# 830-00011_Microhard_Module_Breakout_Boar.net
KiCad netlist of a schematic drawn in Altium Designer
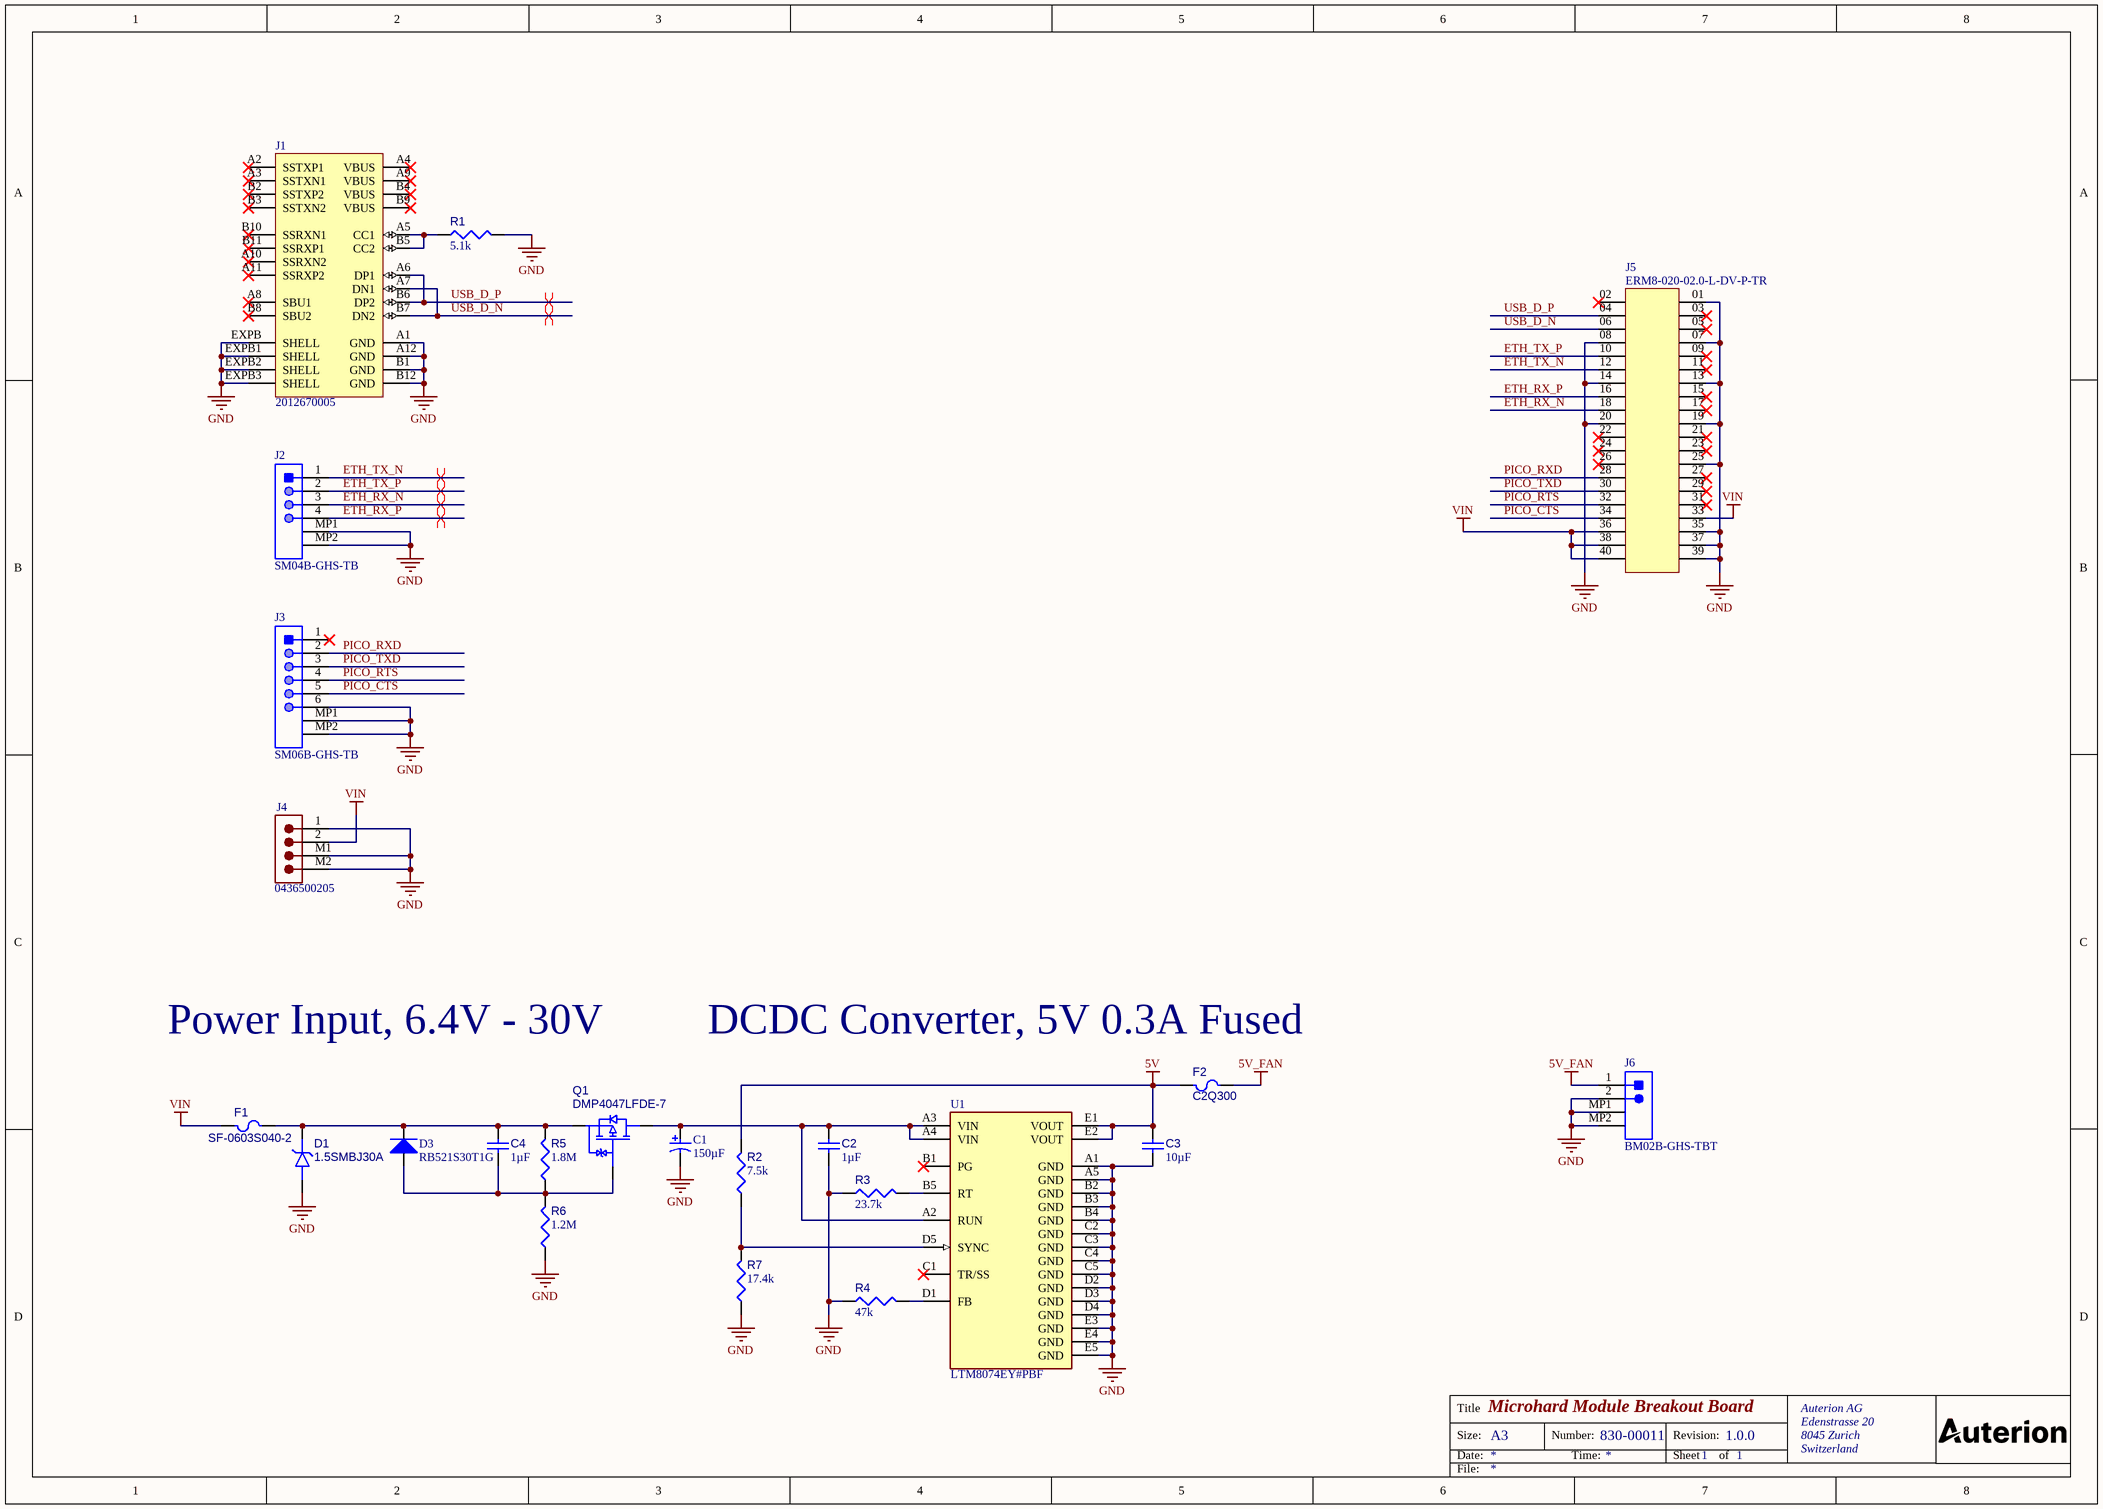
[diagram p0: 830-00011 Microhard Module Breakout Board.SchDoc]

(export (version "E")
  (design (tool "Eeschema 10.0.6"))
  (components
    (comp (ref "C1")
      (value "150µF")
      (footprint "CAPAE6866X82L")
      (description "CAP ALUM 150UF 20% 35V SMD")
      (fields
        (field (name "MANUFACTURER") "Nichicon")
        (field (name "MANUFACTURER PART NUMBER") "UCM1V151MCL1GS")
      )
      (libsource (lib "Auterion AG") (part "CAP-P-2"))
    )
    (comp (ref "C2")
      (value "1µF")
      (footprint "CAPC0603(1608)100_L")
      (description "CAP CER 1UF 50V X5R 0603")
      (fields
        (field (name "TOLERANCE") "10%")
        (field (name "MANUFACTURER PART NUMBER") "C1608X5R1H105K080AB")
      )
      (libsource (lib "Auterion AG") (part "CAP-NP-2"))
    )
    (comp (ref "C3")
      (value "10µF")
      (footprint "CAPC0805(2012)145_L")
      (description "CAP CER 10UF 16V X7R 0805")
      (fields (field (name "TOLERANCE") "20%") (field (name "MANUFACTURER") "Taiyo Yuden"))
      (libsource (lib "Auterion AG") (part "CAP-NP-2"))
    )
    (comp (ref "C4")
      (value "1µF")
      (footprint "CAPC0402(1005)60_L")
      (description "CAP CER 1UF 35V X5R 0402")
      (fields (field (name "TOLERANCE") "10%") (field (name "MANUFACTURER") "TDK Corporation"))
      (libsource (lib "Auterion AG") (part "CAP-NP-2"))
    )
    (comp (ref "D1")
      (value "1.5SMBJ30A")
      (footprint "JCET-SMB-2_N")
      (description "TVS Diode Single Uni-Dir 30V 1.5KW 2-Pin SMB T/R")
      (fields (field (name "MANUFACTURER") "Bourns"))
      (libsource (lib "Auterion AG") (part "D-TVS-AK-2"))
    )
    (comp (ref "D3")
      (value "RB521S30T1G")
      (footprint "ONSC-SOD-523-2-502-01_V")
      (description "Rectifier Diode, Schottky, 1 Phase, 1 Element, 0.2A, 30V V(RRM), Silicon")
      (fields (field (name "MANUFACTURER") "onsemi"))
      (libsource (lib "Auterion AG") (part "ONSC-D-K1A2-2"))
    )
    (comp (ref "F1")
      (value "SF-0603S040-2")
      (footprint "RESC0603(1608)_L")
      (description "Electric Fuse, Slow Blow, 0.4A, 35VAC, 50VDC, 50A (IR), Surface Mount, 0603")
      (fields (field (name "MANUFACTURER") "Bourns Inc."))
      (libsource (lib "Auterion AG") (part "FUSE-2"))
    )
    (comp (ref "F2")
      (value "C2Q300")
      (footprint "RESC0603(1608)_L")
      (description "Electric Fuse, Very Fast Blow, 0.3A, 32VAC, 63VDC, 35A (IR), Surface Mount, 0603")
      (fields
        (field (name "MANUFACTURER PART NUMBER") "C2Q 300")
        (field (name "MANUFACTURER") "Bel Fuse Inc.")
      )
      (libsource (lib "Auterion AG") (part "FUSE-2"))
    )
    (comp (ref "J1")
      (value "2012670005")
      (footprint "2012670005")
      (description "USB Connector, 24 Contact(s), Female, Right Angle, Surface Mount Terminal, Locking, Receptacle")
      (fields
        (field (name "MANUFACTURER") "Molex")
        (field (name "UPDATED BY") "aklimaj")
        (field (name "SOURCE") "skynode_v2_base.SCHLIB")
        (field (name "CREATED BY") "aklimaj")
      )
      (libsource (lib "Auterion AG") (part "30530"))
    )
    (comp (ref "J2")
      (value "SM04B-GHS-TB")
      (footprint "JST-SM04B-GHS-TB")
      (description "4 Positions Header Connector 1.25mm SMD Right Angle")
      (fields (field (name "SFL PART NUMBER") "10751") (field (name "MANUFACTURER") "JST"))
      (libsource (lib "Auterion AG") (part "SM04B-GHS-TB"))
    )
    (comp (ref "J3")
      (value "SM06B-GHS-TB")
      (footprint "JST-SM06B-GHS-TB_V")
      (fields
        (field (name "SFL PART NUMBER") "10703")
        (field (name "MANUFACTURER PART NUMBER") "SM06B-GHS-TB(LF)(SN)")
        (field (name "MANUFACTURER") "JST")
      )
      (libsource (lib "Auterion AG") (part "SM06B-GHS-TB"))
    )
    (comp (ref "J4")
      (value "0436500205")
      (footprint "SHDRRA2W64P300_2X1_965X990H437")
      (description "CONN MALE HEADER R/A 2POS 3MM")
      (fields (field (name "MANUFACTURER") "Molex"))
      (libsource (lib "Auterion AG") (part "CONN_HDR_1x2_MALE_3.00MM_RA_TH"))
    )
    (comp (ref "J5")
      (value "ERM8-020-02.0-L-DV-P-TR")
      (footprint "FP-ERM8-020-02_0-L-DV-TR-MFG")
      (fields (field (name "MANUFACTURER") "Samtec"))
      (libsource (lib "Auterion AG") (part "ERF8-020-XX.X-X-DV-K-XX"))
    )
    (comp (ref "J6")
      (value "BM02B-GHS-TBT")
      (footprint "JST-BM02B-GHS-TBT_V")
      (fields (field (name "MANUFACTURER") "JST Sales America Inc."))
      (libsource (lib "Auterion AG") (part "B2W - BM02B-GHS-TBT"))
    )
    (comp (ref "Q1")
      (value "DMP4047LFDE-7")
      (footprint "DMP2066UFDE7")
      (description "MOSFET P-CH 40V 3.3A 6UDFN")
      (fields (field (name "POWER") "700mW") (field (name "MANUFACTURER") "Diodes Incorporated"))
      (libsource (lib "Auterion AG") (part "CMP-00006-6"))
    )
    (comp (ref "R1")
      (value "5.1k")
      (footprint "RESC0402(1005)_L")
      (fields
        (field (name "MANUFACTURER PART NUMBER") "RC0402JR-075K1L")
        (field (name "TOLERANCE") "5%")
        (field (name "POWER") "63mW")
      )
      (libsource (lib "Auterion AG") (part "RES-2"))
    )
    (comp (ref "R2")
      (value "7.5k")
      (footprint "RESC0402(1005)_L")
      (description "RES 7.5K OHM 1% 1/16W 0402")
      (fields (field (name "POWER") "63mW") (field (name "TOLERANCE") "1%"))
      (libsource (lib "Auterion AG") (part "RES-2"))
    )
    (comp (ref "R3")
      (value "23.7k")
      (footprint "RESC0402(1005)_L")
      (description "RES 23.7K OHM 1% 1/16W 0402")
      (fields (field (name "POWER") "63mW") (field (name "TOLERANCE") "1%"))
      (libsource (lib "Auterion AG") (part "RES-2"))
    )
    (comp (ref "R4")
      (value "47k")
      (footprint "RESC0402(1005)_L")
      (fields
        (field (name "MANUFACTURER") "Yageo")
        (field (name "TOLERANCE") "1%")
        (field (name "MANUFACTURER PART NUMBER") "RC0402FR-0747KL")
      )
      (libsource (lib "Auterion AG") (part "RES-2"))
    )
    (comp (ref "R5")
      (value "1.8M")
      (footprint "RESC0402(1005)_L")
      (description "RES SMD 1.8M OHM 1% 1/16W 0402")
      (fields (field (name "MANUFACTURER") "Samsung Electro-Mechanics") (field (name "POWER") "63mW"))
      (libsource (lib "Auterion AG") (part "RES-2"))
    )
    (comp (ref "R6")
      (value "1.2M")
      (footprint "RESC0402(1005)_L")
      (fields
        (field (name "MANUFACTURER") "Yageo")
        (field (name "MANUFACTURER PART NUMBER") "RC0402FR-071M2L")
        (field (name "TOLERANCE") "1%")
      )
      (libsource (lib "Auterion AG") (part "RES-2"))
    )
    (comp (ref "R7")
      (value "17.4k")
      (footprint "RESC0402(1005)_L")
      (description "RES SMD 17.4K OHM 1% 1/16W 0402")
      (fields (field (name "MANUFACTURER") "Vishay Dale") (field (name "TOLERANCE") "1%"))
      (libsource (lib "Auterion AG") (part "RES-2"))
    )
    (comp (ref "U1")
      (value "LTM8074EY#PBF")
      (footprint "FP-BGA-25-05-08-1566-MFG")
      (description "Switching Regulator, Current-mode, 2200kHz Switching Freq-Max, PBGA25")
      (fields (field (name "MANUFACTURER") "Analog Devices"))
      (libsource (lib "Auterion AG") (part "9e9da4b837be4f4c72679088a9770a1"))
    )
  )
  (nets
    (net (code "1") (name "/ETH_RX_N") (class "Default")
      (node (ref "J2") (pin "3") (pinfunction "3_3") (pintype "passive"))
      (node (ref "J5") (pin "18") (pinfunction "18_18") (pintype "passive"))
    )
    (net (code "2") (name "/ETH_RX_P") (class "Default")
      (node (ref "J2") (pin "4") (pinfunction "4_4") (pintype "passive"))
      (node (ref "J5") (pin "16") (pinfunction "16_16") (pintype "passive"))
    )
    (net (code "3") (name "/ETH_TX_N") (class "Default")
      (node (ref "J2") (pin "1") (pinfunction "1_1") (pintype "passive"))
      (node (ref "J5") (pin "12") (pinfunction "12_12") (pintype "passive"))
    )
    (net (code "4") (name "/ETH_TX_P") (class "Default")
      (node (ref "J2") (pin "2") (pinfunction "2_2") (pintype "passive"))
      (node (ref "J5") (pin "10") (pinfunction "10_10") (pintype "passive"))
    )
    (net (code "5") (name "/PICO_CTS") (class "Default")
      (node (ref "J3") (pin "5") (pinfunction "5_5") (pintype "passive"))
      (node (ref "J5") (pin "34") (pinfunction "34_34") (pintype "passive"))
    )
    (net (code "6") (name "/PICO_RTS") (class "Default")
      (node (ref "J3") (pin "4") (pinfunction "4_4") (pintype "passive"))
      (node (ref "J5") (pin "32") (pinfunction "32_32") (pintype "passive"))
    )
    (net (code "7") (name "/PICO_RXD") (class "Default")
      (node (ref "J3") (pin "2") (pinfunction "2_2") (pintype "passive"))
      (node (ref "J5") (pin "28") (pinfunction "28_28") (pintype "passive"))
    )
    (net (code "8") (name "/PICO_TXD") (class "Default")
      (node (ref "J3") (pin "3") (pinfunction "3_3") (pintype "passive"))
      (node (ref "J5") (pin "30") (pinfunction "30_30") (pintype "passive"))
    )
    (net (code "9") (name "/USB_D_N") (class "Default")
      (node (ref "J1") (pin "A7") (pinfunction "DN1_A7") (pintype "bidirectional"))
      (node (ref "J1") (pin "B7") (pinfunction "DN2_B7") (pintype "bidirectional"))
      (node (ref "J5") (pin "06") (pinfunction "06_06") (pintype "passive"))
    )
    (net (code "10") (name "/USB_D_P") (class "Default")
      (node (ref "J1") (pin "A6") (pinfunction "DP1_A6") (pintype "bidirectional"))
      (node (ref "J1") (pin "B6") (pinfunction "DP2_B6") (pintype "bidirectional"))
      (node (ref "J5") (pin "04") (pinfunction "04_04") (pintype "passive"))
    )
    (net (code "11") (name "5V") (class "Default")
      (node (ref "C3") (pin "2") (pinfunction "2_2") (pintype "passive"))
      (node (ref "F2") (pin "1") (pinfunction "1_1") (pintype "passive"))
      (node (ref "R2") (pin "2") (pinfunction "2_2") (pintype "passive"))
      (node (ref "U1") (pin "E1") (pinfunction "VOUT_E1") (pintype "power_in"))
      (node (ref "U1") (pin "E2") (pinfunction "VOUT_E2") (pintype "power_in"))
    )
    (net (code "12") (name "5V_FAN") (class "Default")
      (node (ref "F2") (pin "2") (pinfunction "2_2") (pintype "passive"))
      (node (ref "J6") (pin "1") (pinfunction "1_1") (pintype "passive"))
    )
    (net (code "13") (name "GND") (class "Default")
      (node (ref "C1") (pin "2") (pinfunction "2_2") (pintype "passive"))
      (node (ref "C2") (pin "1") (pinfunction "1_1") (pintype "passive"))
      (node (ref "C3") (pin "1") (pinfunction "1_1") (pintype "passive"))
      (node (ref "D1") (pin "A") (pinfunction "A_A") (pintype "passive"))
      (node (ref "J1") (pin "A1") (pinfunction "GND_A1") (pintype "power_in"))
      (node (ref "J1") (pin "A12") (pinfunction "GND_A12") (pintype "power_in"))
      (node (ref "J1") (pin "B1") (pinfunction "GND_B1") (pintype "power_in"))
      (node (ref "J1") (pin "B12") (pinfunction "GND_B12") (pintype "power_in"))
      (node (ref "J1") (pin "EXPB") (pinfunction "SHELL_EXPB") (pintype "power_in"))
      (node (ref "J1") (pin "EXPB1") (pinfunction "SHELL_EXPB1") (pintype "power_in"))
      (node (ref "J1") (pin "EXPB2") (pinfunction "SHELL_EXPB2") (pintype "power_in"))
      (node (ref "J1") (pin "EXPB3") (pinfunction "SHELL_EXPB3") (pintype "power_in"))
      (node (ref "J2") (pin "MP1") (pinfunction "MP1_MP1") (pintype "passive"))
      (node (ref "J2") (pin "MP2") (pinfunction "MP2_MP2") (pintype "passive"))
      (node (ref "J3") (pin "6") (pinfunction "6_6") (pintype "passive"))
      (node (ref "J3") (pin "MP1") (pinfunction "MP1_MP1") (pintype "passive"))
      (node (ref "J3") (pin "MP2") (pinfunction "MP2_MP2") (pintype "passive"))
      (node (ref "J4") (pin "1") (pinfunction "1_1") (pintype "passive"))
      (node (ref "J4") (pin "M1") (pinfunction "M1_M1") (pintype "passive"))
      (node (ref "J4") (pin "M2") (pinfunction "M2_M2") (pintype "passive"))
      (node (ref "J5") (pin "01") (pinfunction "01_01") (pintype "passive"))
      (node (ref "J5") (pin "07") (pinfunction "07_07") (pintype "passive"))
      (node (ref "J5") (pin "08") (pinfunction "08_08") (pintype "passive"))
      (node (ref "J5") (pin "13") (pinfunction "13_13") (pintype "passive"))
      (node (ref "J5") (pin "14") (pinfunction "14_14") (pintype "passive"))
      (node (ref "J5") (pin "19") (pinfunction "19_19") (pintype "passive"))
      (node (ref "J5") (pin "20") (pinfunction "20_20") (pintype "passive"))
      (node (ref "J5") (pin "25") (pinfunction "25_25") (pintype "passive"))
      (node (ref "J5") (pin "35") (pinfunction "35_35") (pintype "passive"))
      (node (ref "J5") (pin "37") (pinfunction "37_37") (pintype "passive"))
      (node (ref "J5") (pin "39") (pinfunction "39_39") (pintype "passive"))
      (node (ref "J6") (pin "2") (pinfunction "2_2") (pintype "passive"))
      (node (ref "J6") (pin "MP1") (pinfunction "MP1_MP1") (pintype "passive"))
      (node (ref "J6") (pin "MP2") (pinfunction "MP2_MP2") (pintype "passive"))
      (node (ref "R1") (pin "2") (pinfunction "2_2") (pintype "passive"))
      (node (ref "R3") (pin "1") (pinfunction "1_1") (pintype "passive"))
      (node (ref "R4") (pin "1") (pinfunction "1_1") (pintype "passive"))
      (node (ref "R6") (pin "1") (pinfunction "1_1") (pintype "passive"))
      (node (ref "R7") (pin "1") (pinfunction "1_1") (pintype "passive"))
      (node (ref "U1") (pin "A1") (pinfunction "GND_A1") (pintype "power_in"))
      (node (ref "U1") (pin "A5") (pinfunction "GND_A5") (pintype "power_in"))
      (node (ref "U1") (pin "B2") (pinfunction "GND_B2") (pintype "power_in"))
      (node (ref "U1") (pin "B3") (pinfunction "GND_B3") (pintype "power_in"))
      (node (ref "U1") (pin "B4") (pinfunction "GND_B4") (pintype "power_in"))
      (node (ref "U1") (pin "C2") (pinfunction "GND_C2") (pintype "power_in"))
      (node (ref "U1") (pin "C3") (pinfunction "GND_C3") (pintype "power_in"))
      (node (ref "U1") (pin "C4") (pinfunction "GND_C4") (pintype "power_in"))
      (node (ref "U1") (pin "C5") (pinfunction "GND_C5") (pintype "power_in"))
      (node (ref "U1") (pin "D2") (pinfunction "GND_D2") (pintype "power_in"))
      (node (ref "U1") (pin "D3") (pinfunction "GND_D3") (pintype "power_in"))
      (node (ref "U1") (pin "D4") (pinfunction "GND_D4") (pintype "power_in"))
      (node (ref "U1") (pin "E3") (pinfunction "GND_E3") (pintype "power_in"))
      (node (ref "U1") (pin "E4") (pinfunction "GND_E4") (pintype "power_in"))
      (node (ref "U1") (pin "E5") (pinfunction "GND_E5") (pintype "power_in"))
    )
    (net (code "14") (name "Net-(D3-A)") (class "Default")
      (node (ref "C4") (pin "1") (pinfunction "1_1") (pintype "passive"))
      (node (ref "D3") (pin "2") (pinfunction "A_2") (pintype "passive"))
      (node (ref "Q1") (pin "G") (pinfunction "G_G") (pintype "passive"))
      (node (ref "R5") (pin "1") (pinfunction "1_1") (pintype "passive"))
      (node (ref "R6") (pin "2") (pinfunction "2_2") (pintype "passive"))
    )
    (net (code "15") (name "Net-(D3-K)") (class "Default")
      (node (ref "C4") (pin "2") (pinfunction "2_2") (pintype "passive"))
      (node (ref "D1") (pin "K") (pinfunction "K_K") (pintype "passive"))
      (node (ref "D3") (pin "1") (pinfunction "K_1") (pintype "passive"))
      (node (ref "F1") (pin "2") (pinfunction "2_2") (pintype "passive"))
      (node (ref "Q1") (pin "S") (pinfunction "S_S") (pintype "passive"))
      (node (ref "R5") (pin "2") (pinfunction "2_2") (pintype "passive"))
    )
    (net (code "16") (name "Net-(J1-CC1)") (class "Default")
      (node (ref "J1") (pin "A5") (pinfunction "CC1_A5") (pintype "bidirectional"))
      (node (ref "J1") (pin "B5") (pinfunction "CC2_B5") (pintype "bidirectional"))
      (node (ref "R1") (pin "1") (pinfunction "1_1") (pintype "passive"))
    )
    (net (code "17") (name "Net-(U1-FB)") (class "Default")
      (node (ref "R4") (pin "2") (pinfunction "2_2") (pintype "passive"))
      (node (ref "U1") (pin "D1") (pinfunction "FB_D1") (pintype "passive"))
    )
    (net (code "18") (name "Net-(U1-RT)") (class "Default")
      (node (ref "R3") (pin "2") (pinfunction "2_2") (pintype "passive"))
      (node (ref "U1") (pin "B5") (pinfunction "RT_B5") (pintype "passive"))
    )
    (net (code "19") (name "Net-(U1-RUN)") (class "Default")
      (node (ref "C1") (pin "1") (pinfunction "1_1") (pintype "passive"))
      (node (ref "C2") (pin "2") (pinfunction "2_2") (pintype "passive"))
      (node (ref "Q1") (pin "D") (pinfunction "D_D") (pintype "passive"))
      (node (ref "U1") (pin "A2") (pinfunction "RUN_A2") (pintype "passive"))
      (node (ref "U1") (pin "A3") (pinfunction "VIN_A3") (pintype "power_in"))
      (node (ref "U1") (pin "A4") (pinfunction "VIN_A4") (pintype "power_in"))
    )
    (net (code "20") (name "Net-(U1-SYNC)") (class "Default")
      (node (ref "R2") (pin "1") (pinfunction "1_1") (pintype "passive"))
      (node (ref "R7") (pin "2") (pinfunction "2_2") (pintype "passive"))
      (node (ref "U1") (pin "D5") (pinfunction "SYNC_D5") (pintype "input"))
    )
    (net (code "21") (name "VIN") (class "Default")
      (node (ref "F1") (pin "1") (pinfunction "1_1") (pintype "passive"))
      (node (ref "J4") (pin "2") (pinfunction "2_2") (pintype "passive"))
      (node (ref "J5") (pin "33") (pinfunction "33_33") (pintype "passive"))
      (node (ref "J5") (pin "36") (pinfunction "36_36") (pintype "passive"))
      (node (ref "J5") (pin "38") (pinfunction "38_38") (pintype "passive"))
      (node (ref "J5") (pin "40") (pinfunction "40_40") (pintype "passive"))
    )
    (net (code "22") (name "unconnected-(J1-SBU1-PadA8)") (class "Default")
      (node (ref "J1") (pin "A8") (pinfunction "SBU1_A8") (pintype "passive+no_connect"))
    )
    (net (code "23") (name "unconnected-(J1-SBU2-PadB8)") (class "Default")
      (node (ref "J1") (pin "B8") (pinfunction "SBU2_B8") (pintype "passive+no_connect"))
    )
    (net (code "24") (name "unconnected-(J1-SSRXN1-PadB10)") (class "Default")
      (node (ref "J1") (pin "B10") (pinfunction "SSRXN1_B10") (pintype "passive+no_connect"))
    )
    (net (code "25") (name "unconnected-(J1-SSRXN2-PadA10)") (class "Default")
      (node (ref "J1") (pin "A10") (pinfunction "SSRXN2_A10") (pintype "passive+no_connect"))
    )
    (net (code "26") (name "unconnected-(J1-SSRXP1-PadB11)") (class "Default")
      (node (ref "J1") (pin "B11") (pinfunction "SSRXP1_B11") (pintype "passive+no_connect"))
    )
    (net (code "27") (name "unconnected-(J1-SSRXP2-PadA11)") (class "Default")
      (node (ref "J1") (pin "A11") (pinfunction "SSRXP2_A11") (pintype "passive+no_connect"))
    )
    (net (code "28") (name "unconnected-(J1-SSTXN1-PadA3)") (class "Default")
      (node (ref "J1") (pin "A3") (pinfunction "SSTXN1_A3") (pintype "passive+no_connect"))
    )
    (net (code "29") (name "unconnected-(J1-SSTXN2-PadB3)") (class "Default")
      (node (ref "J1") (pin "B3") (pinfunction "SSTXN2_B3") (pintype "passive+no_connect"))
    )
    (net (code "30") (name "unconnected-(J1-SSTXP1-PadA2)") (class "Default")
      (node (ref "J1") (pin "A2") (pinfunction "SSTXP1_A2") (pintype "passive+no_connect"))
    )
    (net (code "31") (name "unconnected-(J1-SSTXP2-PadB2)") (class "Default")
      (node (ref "J1") (pin "B2") (pinfunction "SSTXP2_B2") (pintype "passive+no_connect"))
    )
    (net (code "32") (name "unconnected-(J1-VBUS-PadA4)") (class "Default")
      (node (ref "J1") (pin "A4") (pinfunction "VBUS_A4") (pintype "power_in+no_connect"))
    )
    (net (code "33") (name "unconnected-(J1-VBUS-PadA9)") (class "Default")
      (node (ref "J1") (pin "A9") (pinfunction "VBUS_A9") (pintype "power_in+no_connect"))
    )
    (net (code "34") (name "unconnected-(J1-VBUS-PadB4)") (class "Default")
      (node (ref "J1") (pin "B4") (pinfunction "VBUS_B4") (pintype "power_in+no_connect"))
    )
    (net (code "35") (name "unconnected-(J1-VBUS-PadB9)") (class "Default")
      (node (ref "J1") (pin "B9") (pinfunction "VBUS_B9") (pintype "power_in+no_connect"))
    )
    (net (code "36") (name "unconnected-(J3-Pad1)") (class "Default")
      (node (ref "J3") (pin "1") (pinfunction "1_1") (pintype "passive+no_connect"))
    )
    (net (code "37") (name "unconnected-(J5-Pad02)") (class "Default")
      (node (ref "J5") (pin "02") (pinfunction "02_02") (pintype "passive+no_connect"))
    )
    (net (code "38") (name "unconnected-(J5-Pad03)") (class "Default")
      (node (ref "J5") (pin "03") (pinfunction "03_03") (pintype "passive+no_connect"))
    )
    (net (code "39") (name "unconnected-(J5-Pad05)") (class "Default")
      (node (ref "J5") (pin "05") (pinfunction "05_05") (pintype "passive+no_connect"))
    )
    (net (code "40") (name "unconnected-(J5-Pad09)") (class "Default")
      (node (ref "J5") (pin "09") (pinfunction "09_09") (pintype "passive+no_connect"))
    )
    (net (code "41") (name "unconnected-(J5-Pad11)") (class "Default")
      (node (ref "J5") (pin "11") (pinfunction "11_11") (pintype "passive+no_connect"))
    )
    (net (code "42") (name "unconnected-(J5-Pad15)") (class "Default")
      (node (ref "J5") (pin "15") (pinfunction "15_15") (pintype "passive+no_connect"))
    )
    (net (code "43") (name "unconnected-(J5-Pad17)") (class "Default")
      (node (ref "J5") (pin "17") (pinfunction "17_17") (pintype "passive+no_connect"))
    )
    (net (code "44") (name "unconnected-(J5-Pad21)") (class "Default")
      (node (ref "J5") (pin "21") (pinfunction "21_21") (pintype "passive+no_connect"))
    )
    (net (code "45") (name "unconnected-(J5-Pad22)") (class "Default")
      (node (ref "J5") (pin "22") (pinfunction "22_22") (pintype "passive+no_connect"))
    )
    (net (code "46") (name "unconnected-(J5-Pad23)") (class "Default")
      (node (ref "J5") (pin "23") (pinfunction "23_23") (pintype "passive+no_connect"))
    )
    (net (code "47") (name "unconnected-(J5-Pad24)") (class "Default")
      (node (ref "J5") (pin "24") (pinfunction "24_24") (pintype "passive+no_connect"))
    )
    (net (code "48") (name "unconnected-(J5-Pad26)") (class "Default")
      (node (ref "J5") (pin "26") (pinfunction "26_26") (pintype "passive+no_connect"))
    )
    (net (code "49") (name "unconnected-(J5-Pad27)") (class "Default")
      (node (ref "J5") (pin "27") (pinfunction "27_27") (pintype "passive+no_connect"))
    )
    (net (code "50") (name "unconnected-(J5-Pad29)") (class "Default")
      (node (ref "J5") (pin "29") (pinfunction "29_29") (pintype "passive+no_connect"))
    )
    (net (code "51") (name "unconnected-(J5-Pad31)") (class "Default")
      (node (ref "J5") (pin "31") (pinfunction "31_31") (pintype "passive+no_connect"))
    )
    (net (code "52") (name "unconnected-(U1-PG-PadB1)") (class "Default")
      (node (ref "U1") (pin "B1") (pinfunction "PG_B1") (pintype "open_collector+no_connect"))
    )
    (net (code "53") (name "unconnected-(U1-TR{slash}SS-PadC1)") (class "Default")
      (node (ref "U1") (pin "C1") (pinfunction "TR/SS_C1") (pintype "passive+no_connect"))
    )
  )
)
